# minigame.net
KiCad netlist of a schematic drawn in EAGLE
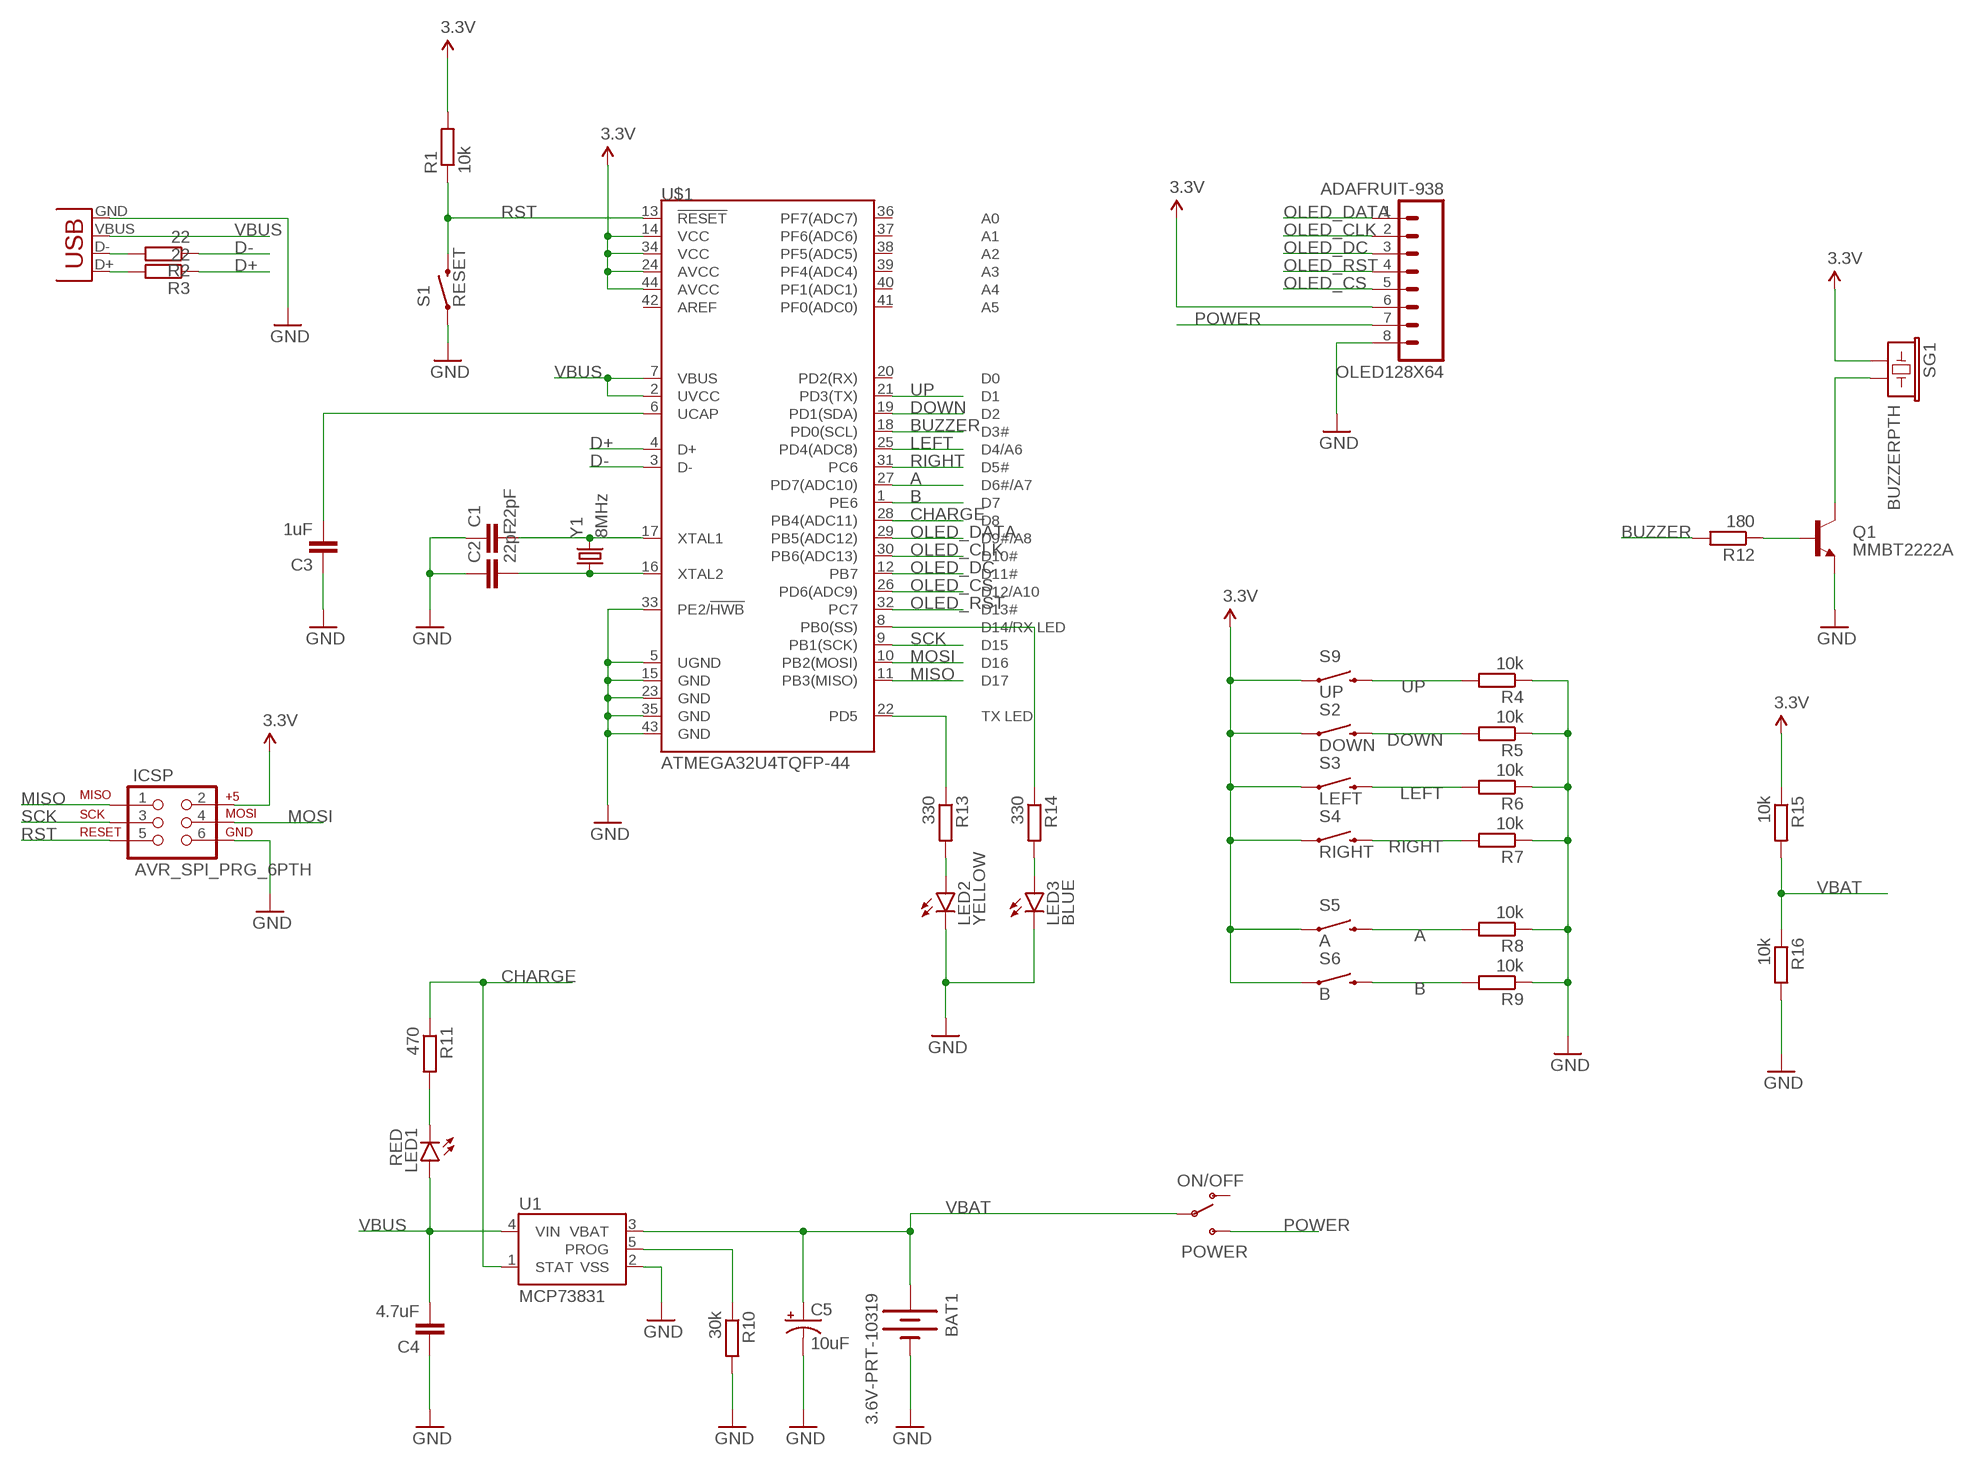
[diagram p0: schematic, sheet 1]

(export (version "E")
  (design (tool "Eeschema 10.0.6"))
  (components
    (comp (ref "BAT1")
      (value "3.6V-PRT-10319")
      (footprint "eagle-import:BATTCON_245MM_PTH")
      (libsource (lib "eagle-import") (part "BATTERY245PTH"))
    )
    (comp (ref "C1")
      (value "22pF")
      (footprint "eagle-import:1206")
      (libsource (lib "eagle-import") (part "CAP1206"))
    )
    (comp (ref "C2")
      (value "22pF")
      (footprint "eagle-import:1206")
      (libsource (lib "eagle-import") (part "CAP1206"))
    )
    (comp (ref "C3")
      (value "1uF")
      (footprint "eagle-import:1206")
      (libsource (lib "eagle-import") (part "CAP1206"))
    )
    (comp (ref "C4")
      (value "4.7uF")
      (footprint "eagle-import:1206")
      (libsource (lib "eagle-import") (part "CAP1206"))
    )
    (comp (ref "C5")
      (value "10uF")
      (footprint "eagle-import:PANASONIC_D")
      (libsource (lib "eagle-import") (part "CAP_POLD"))
    )
    (comp (ref "ICSP")
      (value "AVR_SPI_PRG_6PTH")
      (footprint "eagle-import:2X3")
      (libsource (lib "eagle-import") (part "AVR_SPI_PRG_6PTH"))
    )
    (comp (ref "JP1")
      (value "USB-SMD-NS")
      (footprint "eagle-import:USB-MINIB-NOSTOP")
      (libsource (lib "eagle-import") (part "USB-SMD-NS"))
    )
    (comp (ref "LED1")
      (value "RED")
      (footprint "eagle-import:LED-0603")
      (libsource (lib "eagle-import") (part "LED0603"))
    )
    (comp (ref "LED2")
      (value "YELLOW")
      (footprint "eagle-import:LED-0603")
      (libsource (lib "eagle-import") (part "LED0603"))
    )
    (comp (ref "LED3")
      (value "BLUE")
      (footprint "eagle-import:LED-0603")
      (libsource (lib "eagle-import") (part "LED0603"))
    )
    (comp (ref "OLED128X64")
      (value "ADAFRUIT-938")
      (footprint "eagle-import:1X08_LONGPADS")
      (libsource (lib "eagle-import") (part "M08LONGPADS"))
    )
    (comp (ref "POWER")
      (value "ON/OFF")
      (footprint "eagle-import:AYZ0202")
      (libsource (lib "eagle-import") (part "SWITCH-SPDTSMD"))
    )
    (comp (ref "Q1")
      (value "MMBT2222A")
      (footprint "eagle-import:SOT23-3")
      (libsource (lib "eagle-import") (part "TRANSISTOR_NPNMMBT2222A"))
    )
    (comp (ref "R1")
      (value "10k")
      (footprint "eagle-import:M0805")
      (libsource (lib "eagle-import") (part "R-EU_M0805"))
    )
    (comp (ref "R2")
      (value "22")
      (footprint "eagle-import:M0805")
      (libsource (lib "eagle-import") (part "R-EU_M0805"))
    )
    (comp (ref "R3")
      (value "22")
      (footprint "eagle-import:M0805")
      (libsource (lib "eagle-import") (part "R-EU_M0805"))
    )
    (comp (ref "R4")
      (value "10k")
      (footprint "eagle-import:M0805")
      (libsource (lib "eagle-import") (part "R-EU_M0805"))
    )
    (comp (ref "R5")
      (value "10k")
      (footprint "eagle-import:M0805")
      (libsource (lib "eagle-import") (part "R-EU_M0805"))
    )
    (comp (ref "R6")
      (value "10k")
      (footprint "eagle-import:M0805")
      (libsource (lib "eagle-import") (part "R-EU_M0805"))
    )
    (comp (ref "R7")
      (value "10k")
      (footprint "eagle-import:M0805")
      (libsource (lib "eagle-import") (part "R-EU_M0805"))
    )
    (comp (ref "R8")
      (value "10k")
      (footprint "eagle-import:M0805")
      (libsource (lib "eagle-import") (part "R-EU_M0805"))
    )
    (comp (ref "R9")
      (value "10k")
      (footprint "eagle-import:M0805")
      (libsource (lib "eagle-import") (part "R-EU_M0805"))
    )
    (comp (ref "R10")
      (value "30k")
      (footprint "eagle-import:M0805")
      (libsource (lib "eagle-import") (part "R-EU_M0805"))
    )
    (comp (ref "R11")
      (value "470")
      (footprint "eagle-import:M0805")
      (libsource (lib "eagle-import") (part "R-EU_M0805"))
    )
    (comp (ref "R12")
      (value "180")
      (footprint "eagle-import:M0805")
      (libsource (lib "eagle-import") (part "R-EU_M0805"))
    )
    (comp (ref "R13")
      (value "330")
      (footprint "eagle-import:M0805")
      (libsource (lib "eagle-import") (part "R-EU_M0805"))
    )
    (comp (ref "R14")
      (value "330")
      (footprint "eagle-import:M0805")
      (libsource (lib "eagle-import") (part "R-EU_M0805"))
    )
    (comp (ref "R15")
      (value "10k")
      (footprint "eagle-import:M0805")
      (libsource (lib "eagle-import") (part "R-EU_M0805"))
    )
    (comp (ref "R16")
      (value "10k")
      (footprint "eagle-import:M0805")
      (libsource (lib "eagle-import") (part "R-EU_M0805"))
    )
    (comp (ref "S1")
      (value "RESET")
      (footprint "eagle-import:TACTILE-SWITCH-SMD")
      (libsource (lib "eagle-import") (part "SWITCH-MOMENTARY-2SMD"))
    )
    (comp (ref "S2")
      (value "DOWN")
      (footprint "eagle-import:TACTILE_SWITCH_TALL")
      (libsource (lib "eagle-import") (part "SWITCH-MOMENTARY-2SMD-4"))
    )
    (comp (ref "S3")
      (value "LEFT")
      (footprint "eagle-import:TACTILE_SWITCH_TALL")
      (libsource (lib "eagle-import") (part "SWITCH-MOMENTARY-2SMD-4"))
    )
    (comp (ref "S4")
      (value "RIGHT")
      (footprint "eagle-import:TACTILE_SWITCH_TALL")
      (libsource (lib "eagle-import") (part "SWITCH-MOMENTARY-2SMD-4"))
    )
    (comp (ref "S5")
      (value "A")
      (footprint "eagle-import:TACTILE_SWITCH_TALL")
      (libsource (lib "eagle-import") (part "SWITCH-MOMENTARY-2SMD-4"))
    )
    (comp (ref "S6")
      (value "B")
      (footprint "eagle-import:TACTILE_SWITCH_TALL")
      (libsource (lib "eagle-import") (part "SWITCH-MOMENTARY-2SMD-4"))
    )
    (comp (ref "S9")
      (value "UP")
      (footprint "eagle-import:TACTILE_SWITCH_TALL")
      (libsource (lib "eagle-import") (part "SWITCH-MOMENTARY-2SMD-4"))
    )
    (comp (ref "SG1")
      (value "BUZZERPTH")
      (footprint "eagle-import:BUZZER-12MM")
      (libsource (lib "eagle-import") (part "BUZZERPTH"))
    )
    (comp (ref "U$1")
      (value "ATMEGA32U4TQFP-44")
      (footprint "eagle-import:TQFP44")
      (libsource (lib "eagle-import") (part "ATMEGA32U4TQFP-44"))
    )
    (comp (ref "U1")
      (value "MCP73831")
      (footprint "eagle-import:SOT23-5")
      (libsource (lib "eagle-import") (part "MCP73831"))
    )
    (comp (ref "Y1")
      (value "8MHz")
      (footprint "eagle-import:HC49US")
      (libsource (lib "eagle-import") (part "CRYSTALHC49US"))
    )
  )
  (nets
    (net (code "1") (name "/A") (class "Default")
      (node (ref "R8") (pin "2") (pinfunction "2_2") (pintype "passive"))
      (node (ref "S5") (pin "B2") (pinfunction "2_B2") (pintype "passive"))
      (node (ref "U$1") (pin "27") (pinfunction "PD7(ADC10)_27") (pintype "bidirectional"))
    )
    (net (code "2") (name "/B") (class "Default")
      (node (ref "R9") (pin "2") (pinfunction "2_2") (pintype "passive"))
      (node (ref "S6") (pin "B2") (pinfunction "2_B2") (pintype "passive"))
      (node (ref "U$1") (pin "1") (pinfunction "PE6_1") (pintype "bidirectional"))
    )
    (net (code "3") (name "/BUZZER") (class "Default")
      (node (ref "R12") (pin "2") (pinfunction "2_2") (pintype "passive"))
      (node (ref "U$1") (pin "18") (pinfunction "PD0(SCL)_18") (pintype "bidirectional"))
    )
    (net (code "4") (name "/CHARGE") (class "Default")
      (node (ref "R11") (pin "1") (pinfunction "1_1") (pintype "passive"))
      (node (ref "U$1") (pin "28") (pinfunction "PB4(ADC11)_28") (pintype "bidirectional"))
      (node (ref "U1") (pin "1") (pinfunction "STAT_1") (pintype "output"))
    )
    (net (code "5") (name "/D+") (class "Default")
      (node (ref "R3") (pin "1") (pinfunction "1_1") (pintype "passive"))
      (node (ref "U$1") (pin "4") (pinfunction "D+_4") (pintype "bidirectional"))
    )
    (net (code "6") (name "/D-") (class "Default")
      (node (ref "R2") (pin "1") (pinfunction "1_1") (pintype "passive"))
      (node (ref "U$1") (pin "3") (pinfunction "D-_3") (pintype "bidirectional"))
    )
    (net (code "7") (name "/DOWN") (class "Default")
      (node (ref "R5") (pin "2") (pinfunction "2_2") (pintype "passive"))
      (node (ref "S2") (pin "B2") (pinfunction "2_B2") (pintype "passive"))
      (node (ref "U$1") (pin "19") (pinfunction "PD1(SDA)_19") (pintype "bidirectional"))
    )
    (net (code "8") (name "/LEFT") (class "Default")
      (node (ref "R6") (pin "2") (pinfunction "2_2") (pintype "passive"))
      (node (ref "S3") (pin "B2") (pinfunction "2_B2") (pintype "passive"))
      (node (ref "U$1") (pin "25") (pinfunction "PD4(ADC8)_25") (pintype "bidirectional"))
    )
    (net (code "9") (name "/MISO") (class "Default")
      (node (ref "ICSP") (pin "1") (pinfunction "1_1") (pintype "passive"))
      (node (ref "U$1") (pin "11") (pinfunction "PB3(MISO)_11") (pintype "bidirectional"))
    )
    (net (code "10") (name "/MOSI") (class "Default")
      (node (ref "ICSP") (pin "4") (pinfunction "4_4") (pintype "passive"))
      (node (ref "U$1") (pin "10") (pinfunction "PB2(MOSI)_10") (pintype "bidirectional"))
    )
    (net (code "11") (name "/OLED_CLK") (class "Default")
      (node (ref "OLED128X64") (pin "2") (pinfunction "2_2") (pintype "passive"))
      (node (ref "U$1") (pin "30") (pinfunction "PB6(ADC13)_30") (pintype "bidirectional"))
    )
    (net (code "12") (name "/OLED_CS") (class "Default")
      (node (ref "OLED128X64") (pin "5") (pinfunction "5_5") (pintype "passive"))
      (node (ref "U$1") (pin "26") (pinfunction "PD6(ADC9)_26") (pintype "bidirectional"))
    )
    (net (code "13") (name "/OLED_DATA") (class "Default")
      (node (ref "OLED128X64") (pin "1") (pinfunction "1_1") (pintype "passive"))
      (node (ref "U$1") (pin "29") (pinfunction "PB5(ADC12)_29") (pintype "bidirectional"))
    )
    (net (code "14") (name "/OLED_DC") (class "Default")
      (node (ref "OLED128X64") (pin "3") (pinfunction "3_3") (pintype "passive"))
      (node (ref "U$1") (pin "12") (pinfunction "PB7_12") (pintype "bidirectional"))
    )
    (net (code "15") (name "/OLED_RST") (class "Default")
      (node (ref "OLED128X64") (pin "4") (pinfunction "4_4") (pintype "passive"))
      (node (ref "U$1") (pin "32") (pinfunction "PC7_32") (pintype "bidirectional"))
    )
    (net (code "16") (name "/POWER") (class "Default")
      (node (ref "OLED128X64") (pin "7") (pinfunction "7_7") (pintype "passive"))
      (node (ref "POWER") (pin "3") (pinfunction "S_3") (pintype "passive"))
    )
    (net (code "17") (name "/RIGHT") (class "Default")
      (node (ref "R7") (pin "2") (pinfunction "2_2") (pintype "passive"))
      (node (ref "S4") (pin "B2") (pinfunction "2_B2") (pintype "passive"))
      (node (ref "U$1") (pin "31") (pinfunction "PC6_31") (pintype "bidirectional"))
    )
    (net (code "18") (name "/RST") (class "Default")
      (node (ref "ICSP") (pin "5") (pinfunction "5_5") (pintype "passive"))
      (node (ref "R1") (pin "1") (pinfunction "1_1") (pintype "passive"))
      (node (ref "S1") (pin "3") (pinfunction "2_3") (pintype "passive"))
      (node (ref "U$1") (pin "13") (pinfunction "~{RESET}_13") (pintype "bidirectional"))
    )
    (net (code "19") (name "/SCK") (class "Default")
      (node (ref "ICSP") (pin "3") (pinfunction "3_3") (pintype "passive"))
      (node (ref "U$1") (pin "9") (pinfunction "PB1(SCK)_9") (pintype "bidirectional"))
    )
    (net (code "20") (name "/UP") (class "Default")
      (node (ref "R4") (pin "2") (pinfunction "2_2") (pintype "passive"))
      (node (ref "S9") (pin "B2") (pinfunction "2_B2") (pintype "passive"))
      (node (ref "U$1") (pin "21") (pinfunction "PD3(TX)_21") (pintype "bidirectional"))
    )
    (net (code "21") (name "/VBAT") (class "Default")
      (node (ref "BAT1") (pin "3") (pinfunction "+_3") (pintype "power_in"))
      (node (ref "C5") (pin "+") (pinfunction "+_+") (pintype "passive"))
      (node (ref "POWER") (pin "2") (pinfunction "P_2") (pintype "passive"))
      (node (ref "R15") (pin "2") (pinfunction "2_2") (pintype "passive"))
      (node (ref "R16") (pin "1") (pinfunction "1_1") (pintype "passive"))
      (node (ref "U1") (pin "3") (pinfunction "VBAT_3") (pintype "power_in"))
    )
    (net (code "22") (name "/VBUS") (class "Default")
      (node (ref "C4") (pin "2") (pinfunction "2_2") (pintype "passive"))
      (node (ref "JP1") (pin "VBUS") (pinfunction "VBUS_VBUS") (pintype "bidirectional"))
      (node (ref "LED1") (pin "A") (pinfunction "A_A") (pintype "passive"))
      (node (ref "U$1") (pin "2") (pinfunction "UVCC_2") (pintype "bidirectional"))
      (node (ref "U$1") (pin "7") (pinfunction "VBUS_7") (pintype "bidirectional"))
      (node (ref "U1") (pin "4") (pinfunction "VIN_4") (pintype "power_in"))
    )
    (net (code "23") (name "3.3V") (class "Default")
      (node (ref "ICSP") (pin "2") (pinfunction "2_2") (pintype "passive"))
      (node (ref "OLED128X64") (pin "6") (pinfunction "6_6") (pintype "passive"))
      (node (ref "R1") (pin "2") (pinfunction "2_2") (pintype "passive"))
      (node (ref "R15") (pin "1") (pinfunction "1_1") (pintype "passive"))
      (node (ref "S2") (pin "A2") (pinfunction "1_A2") (pintype "passive"))
      (node (ref "S3") (pin "A2") (pinfunction "1_A2") (pintype "passive"))
      (node (ref "S4") (pin "A2") (pinfunction "1_A2") (pintype "passive"))
      (node (ref "S5") (pin "A2") (pinfunction "1_A2") (pintype "passive"))
      (node (ref "S6") (pin "A2") (pinfunction "1_A2") (pintype "passive"))
      (node (ref "S9") (pin "A2") (pinfunction "1_A2") (pintype "passive"))
      (node (ref "SG1") (pin "+") (pinfunction "1_+") (pintype "passive"))
      (node (ref "U$1") (pin "14") (pinfunction "VCC_14") (pintype "bidirectional"))
      (node (ref "U$1") (pin "24") (pinfunction "AVCC_24") (pintype "bidirectional"))
      (node (ref "U$1") (pin "34") (pinfunction "VCC_34") (pintype "bidirectional"))
      (node (ref "U$1") (pin "44") (pinfunction "AVCC_44") (pintype "bidirectional"))
    )
    (net (code "24") (name "GND") (class "Default")
      (node (ref "BAT1") (pin "2") (pinfunction "-_2") (pintype "power_in"))
      (node (ref "C1") (pin "1") (pinfunction "1_1") (pintype "passive"))
      (node (ref "C2") (pin "1") (pinfunction "1_1") (pintype "passive"))
      (node (ref "C3") (pin "1") (pinfunction "1_1") (pintype "passive"))
      (node (ref "C4") (pin "1") (pinfunction "1_1") (pintype "passive"))
      (node (ref "C5") (pin "-") (pinfunction "-_-") (pintype "passive"))
      (node (ref "ICSP") (pin "6") (pinfunction "6_6") (pintype "passive"))
      (node (ref "JP1") (pin "GND") (pinfunction "GND_GND") (pintype "bidirectional"))
      (node (ref "LED2") (pin "C") (pinfunction "C_C") (pintype "passive"))
      (node (ref "LED3") (pin "C") (pinfunction "C_C") (pintype "passive"))
      (node (ref "OLED128X64") (pin "8") (pinfunction "8_8") (pintype "passive"))
      (node (ref "Q1") (pin "2") (pinfunction "E_2") (pintype "passive"))
      (node (ref "R10") (pin "2") (pinfunction "2_2") (pintype "passive"))
      (node (ref "R16") (pin "2") (pinfunction "2_2") (pintype "passive"))
      (node (ref "R4") (pin "1") (pinfunction "1_1") (pintype "passive"))
      (node (ref "R5") (pin "1") (pinfunction "1_1") (pintype "passive"))
      (node (ref "R6") (pin "1") (pinfunction "1_1") (pintype "passive"))
      (node (ref "R7") (pin "1") (pinfunction "1_1") (pintype "passive"))
      (node (ref "R8") (pin "1") (pinfunction "1_1") (pintype "passive"))
      (node (ref "R9") (pin "1") (pinfunction "1_1") (pintype "passive"))
      (node (ref "S1") (pin "1") (pinfunction "1_1") (pintype "passive"))
      (node (ref "U$1") (pin "15") (pinfunction "GND_15") (pintype "bidirectional"))
      (node (ref "U$1") (pin "23") (pinfunction "GND_23") (pintype "bidirectional"))
      (node (ref "U$1") (pin "33") (pinfunction "PE2/~{HWB}_33") (pintype "bidirectional"))
      (node (ref "U$1") (pin "35") (pinfunction "GND_35") (pintype "bidirectional"))
      (node (ref "U$1") (pin "43") (pinfunction "GND_43") (pintype "bidirectional"))
      (node (ref "U$1") (pin "5") (pinfunction "UGND_5") (pintype "bidirectional"))
      (node (ref "U1") (pin "2") (pinfunction "VSS_2") (pintype "power_in"))
    )
    (net (code "25") (name "Net-(JP1-PadD+)") (class "Default")
      (node (ref "JP1") (pin "D+") (pinfunction "D+_D+") (pintype "bidirectional"))
      (node (ref "R3") (pin "2") (pinfunction "2_2") (pintype "passive"))
    )
    (net (code "26") (name "Net-(JP1-PadD-)") (class "Default")
      (node (ref "JP1") (pin "D-") (pinfunction "D-_D-") (pintype "bidirectional"))
      (node (ref "R2") (pin "2") (pinfunction "2_2") (pintype "passive"))
    )
    (net (code "27") (name "Net-(LED1-PadC)") (class "Default")
      (node (ref "LED1") (pin "C") (pinfunction "C_C") (pintype "passive"))
      (node (ref "R11") (pin "2") (pinfunction "2_2") (pintype "passive"))
    )
    (net (code "28") (name "Net-(LED2-PadA)") (class "Default")
      (node (ref "LED2") (pin "A") (pinfunction "A_A") (pintype "passive"))
      (node (ref "R13") (pin "2") (pinfunction "2_2") (pintype "passive"))
    )
    (net (code "29") (name "Net-(LED3-PadA)") (class "Default")
      (node (ref "LED3") (pin "A") (pinfunction "A_A") (pintype "passive"))
      (node (ref "R14") (pin "2") (pinfunction "2_2") (pintype "passive"))
    )
    (net (code "30") (name "Net-(Q1-B)") (class "Default")
      (node (ref "Q1") (pin "1") (pinfunction "B_1") (pintype "passive"))
      (node (ref "R12") (pin "1") (pinfunction "1_1") (pintype "passive"))
    )
    (net (code "31") (name "Net-(Q1-C)") (class "Default")
      (node (ref "Q1") (pin "3") (pinfunction "C_3") (pintype "passive"))
      (node (ref "SG1") (pin "-") (pinfunction "2_-") (pintype "passive"))
    )
    (net (code "32") (name "Net-(U$1-PB0(SS))") (class "Default")
      (node (ref "R14") (pin "1") (pinfunction "1_1") (pintype "passive"))
      (node (ref "U$1") (pin "8") (pinfunction "PB0(SS)_8") (pintype "bidirectional"))
    )
    (net (code "33") (name "Net-(U$1-PD5)") (class "Default")
      (node (ref "R13") (pin "1") (pinfunction "1_1") (pintype "passive"))
      (node (ref "U$1") (pin "22") (pinfunction "PD5_22") (pintype "bidirectional"))
    )
    (net (code "34") (name "Net-(U$1-UCAP)") (class "Default")
      (node (ref "C3") (pin "2") (pinfunction "2_2") (pintype "passive"))
      (node (ref "U$1") (pin "6") (pinfunction "UCAP_6") (pintype "bidirectional"))
    )
    (net (code "35") (name "Net-(U$1-XTAL1)") (class "Default")
      (node (ref "C1") (pin "2") (pinfunction "2_2") (pintype "passive"))
      (node (ref "U$1") (pin "17") (pinfunction "XTAL1_17") (pintype "bidirectional"))
      (node (ref "Y1") (pin "2") (pinfunction "2_2") (pintype "passive"))
    )
    (net (code "36") (name "Net-(U$1-XTAL2)") (class "Default")
      (node (ref "C2") (pin "2") (pinfunction "2_2") (pintype "passive"))
      (node (ref "U$1") (pin "16") (pinfunction "XTAL2_16") (pintype "bidirectional"))
      (node (ref "Y1") (pin "1") (pinfunction "1_1") (pintype "passive"))
    )
    (net (code "37") (name "Net-(U1-PROG)") (class "Default")
      (node (ref "R10") (pin "1") (pinfunction "1_1") (pintype "passive"))
      (node (ref "U1") (pin "5") (pinfunction "PROG_5") (pintype "input"))
    )
    (net (code "38") (name "unconnected-(POWER-O-Pad1)") (class "Default")
      (node (ref "POWER") (pin "1") (pinfunction "O_1") (pintype "passive"))
    )
    (net (code "39") (name "unconnected-(U$1-AREF-Pad42)") (class "Default")
      (node (ref "U$1") (pin "42") (pinfunction "AREF_42") (pintype "bidirectional"))
    )
    (net (code "40") (name "unconnected-(U$1-PD2(RX)-Pad20)") (class "Default")
      (node (ref "U$1") (pin "20") (pinfunction "PD2(RX)_20") (pintype "bidirectional"))
    )
    (net (code "41") (name "unconnected-(U$1-PF0(ADC0)-Pad41)") (class "Default")
      (node (ref "U$1") (pin "41") (pinfunction "PF0(ADC0)_41") (pintype "bidirectional"))
    )
    (net (code "42") (name "unconnected-(U$1-PF1(ADC1)-Pad40)") (class "Default")
      (node (ref "U$1") (pin "40") (pinfunction "PF1(ADC1)_40") (pintype "bidirectional"))
    )
    (net (code "43") (name "unconnected-(U$1-PF4(ADC4)-Pad39)") (class "Default")
      (node (ref "U$1") (pin "39") (pinfunction "PF4(ADC4)_39") (pintype "bidirectional"))
    )
    (net (code "44") (name "unconnected-(U$1-PF5(ADC5)-Pad38)") (class "Default")
      (node (ref "U$1") (pin "38") (pinfunction "PF5(ADC5)_38") (pintype "bidirectional"))
    )
    (net (code "45") (name "unconnected-(U$1-PF6(ADC6)-Pad37)") (class "Default")
      (node (ref "U$1") (pin "37") (pinfunction "PF6(ADC6)_37") (pintype "bidirectional"))
    )
    (net (code "46") (name "unconnected-(U$1-PF7(ADC7)-Pad36)") (class "Default")
      (node (ref "U$1") (pin "36") (pinfunction "PF7(ADC7)_36") (pintype "bidirectional"))
    )
  )
)
